# Lumos_Probe.net
KiCad netlist of a schematic drawn in Altium Designer
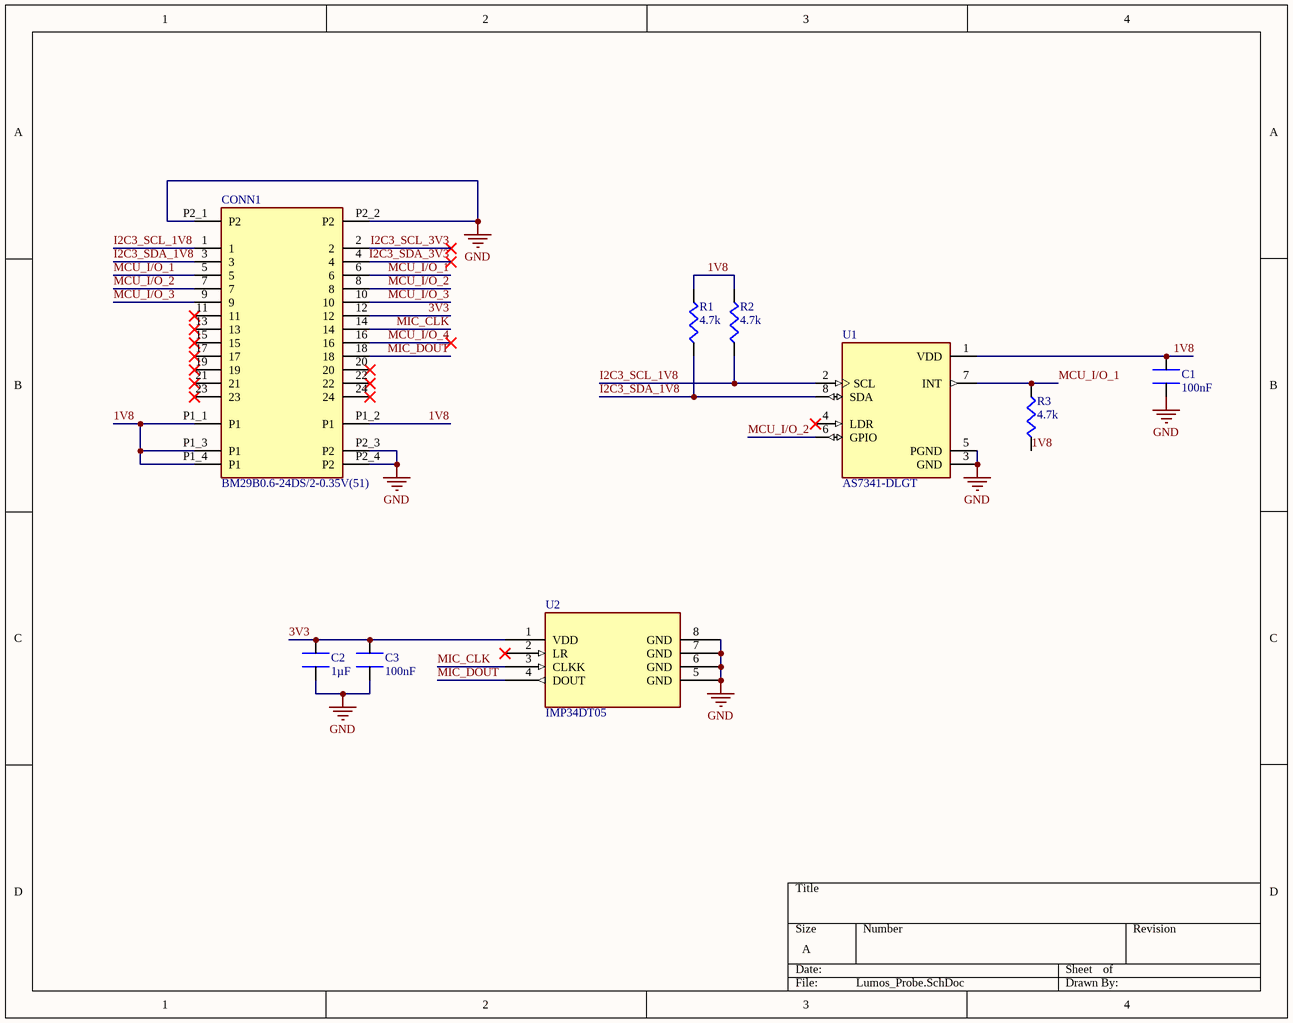
[diagram p0: Lumos_Probe.SchDoc]

(export (version "E")
  (design (tool "Eeschema 10.0.6"))
  (components
    (comp (ref "C1")
      (value "100nF")
      (footprint "Chip2PinSM127P600-8N")
      (fields
        (field (name "MANUFACTURER") "KYOCERA AVX")
        (field (name "MANUFACTURER PART NUMBER") "0402YC104JAT4A")
      )
      (libsource (lib "Lumos_Probe") (part "CMP-00047-1"))
    )
    (comp (ref "C2")
      (value "1µF")
      (footprint "Chip2PinSM127P600-8N")
      (fields
        (field (name "MANUFACTURER") "KYOCERA AVX")
        (field (name "MANUFACTURER PART NUMBER") "0402YD105KAT4A")
      )
      (libsource (lib "Lumos_Probe") (part "CMP-001-00107-6"))
    )
    (comp (ref "C3")
      (value "100nF")
      (footprint "Chip2PinSM127P600-8N")
      (fields
        (field (name "MANUFACTURER") "KYOCERA AVX")
        (field (name "MANUFACTURER PART NUMBER") "0402YC104JAT4A")
      )
      (libsource (lib "Lumos_Probe") (part "CMP-00047-1"))
    )
    (comp (ref "CONN1")
      (value "BM29B0.6-24DS/2-0.35V(51)")
      (footprint "BM29B0.6-24DS_2-0.35V(51)-Footprint-1")
      (description "Connector Receptacle 26 Pos (24+2) SMD")
      (fields (field (name "MANUFACTURER") "HIROSE ELECTRIC"))
      (libsource (lib "Lumos_Probe") (part "CMP-002-00106-1"))
    )
    (comp (ref "R1")
      (value "4.7k")
      (footprint "Chip2PinSM127P600-8N")
      (fields
        (field (name "TOLERANCE") "5%")
        (field (name "POWER") "50mW")
        (field (name "MANUFACTURER") "Bourns")
      )
      (libsource (lib "Lumos_Probe") (part "CMP-00117-1"))
    )
    (comp (ref "R2")
      (value "4.7k")
      (footprint "Chip2PinSM127P600-8N")
      (fields
        (field (name "TOLERANCE") "5%")
        (field (name "POWER") "50mW")
        (field (name "MANUFACTURER") "Bourns")
      )
      (libsource (lib "Lumos_Probe") (part "CMP-00117-1"))
    )
    (comp (ref "R3")
      (value "4.7k")
      (footprint "Chip2PinSM127P600-8N")
      (fields
        (field (name "TOLERANCE") "5%")
        (field (name "POWER") "50mW")
        (field (name "MANUFACTURER") "Bourns")
      )
      (libsource (lib "Lumos_Probe") (part "CMP-00117-1"))
    )
    (comp (ref "U1")
      (value "AS7341-DLGT")
      (footprint "PSON80P310X200X110-8N")
      (description "Optical Sensor Ambient - IÂ²C 8-TFLGA")
      (fields (field (name "MF") "ams"))
      (libsource (lib "Lumos_Probe") (part "AS7341-DLGT"))
    )
    (comp (ref "U2")
      (value "IMP34DT05")
      (footprint "HCLGA_3X4X1_STM")
      (description "MEMS audio sensor omnidirectional digital microphone for industrial applications")
      (fields (field (name "COPYRIGHT") "Copyright (C) 2025 Ultra Librarian. All rights reserved."))
      (libsource (lib "Lumos_Probe") (part "IMP34DT05"))
    )
  )
  (nets
    (net (code "1") (name "/1V8") (class "Default")
      (node (ref "C1") (pin "1") (pinfunction "1_1") (pintype "passive"))
      (node (ref "CONN1") (pin "P1_1") (pinfunction "P1_P1_1") (pintype "power_in"))
      (node (ref "CONN1") (pin "P1_2") (pinfunction "P1_P1_2") (pintype "power_in"))
      (node (ref "CONN1") (pin "P1_3") (pinfunction "P1_P1_3") (pintype "power_in"))
      (node (ref "CONN1") (pin "P1_4") (pinfunction "P1_P1_4") (pintype "power_in"))
      (node (ref "R1") (pin "1") (pinfunction "1_1") (pintype "passive"))
      (node (ref "R2") (pin "1") (pinfunction "1_1") (pintype "passive"))
      (node (ref "R3") (pin "1") (pinfunction "1_1") (pintype "passive"))
      (node (ref "U1") (pin "1") (pinfunction "VDD_1") (pintype "power_in"))
    )
    (net (code "2") (name "/3V3") (class "Default")
      (node (ref "C2") (pin "1") (pinfunction "1_1") (pintype "passive"))
      (node (ref "C3") (pin "1") (pinfunction "1_1") (pintype "passive"))
      (node (ref "CONN1") (pin "12") (pinfunction "12_12") (pintype "passive"))
      (node (ref "U2") (pin "1") (pinfunction "VDD_1") (pintype "power_in"))
    )
    (net (code "3") (name "/I2C3_SCL_1V8") (class "Default")
      (node (ref "CONN1") (pin "1") (pinfunction "1_1") (pintype "passive"))
      (node (ref "R2") (pin "2") (pinfunction "2_2") (pintype "passive"))
      (node (ref "U1") (pin "2") (pinfunction "SCL_2") (pintype "input"))
    )
    (net (code "4") (name "/I2C3_SCL_3V3") (class "Default")
      (node (ref "CONN1") (pin "2") (pinfunction "2_2") (pintype "passive+no_connect"))
    )
    (net (code "5") (name "/I2C3_SDA_1V8") (class "Default")
      (node (ref "CONN1") (pin "3") (pinfunction "3_3") (pintype "passive"))
      (node (ref "R1") (pin "2") (pinfunction "2_2") (pintype "passive"))
      (node (ref "U1") (pin "8") (pinfunction "SDA_8") (pintype "bidirectional"))
    )
    (net (code "6") (name "/I2C3_SDA_3V3") (class "Default")
      (node (ref "CONN1") (pin "4") (pinfunction "4_4") (pintype "passive+no_connect"))
    )
    (net (code "7") (name "/MCU_I{slash}O_1") (class "Default")
      (node (ref "CONN1") (pin "5") (pinfunction "5_5") (pintype "passive"))
      (node (ref "CONN1") (pin "6") (pinfunction "6_6") (pintype "passive"))
      (node (ref "R3") (pin "2") (pinfunction "2_2") (pintype "passive"))
      (node (ref "U1") (pin "7") (pinfunction "INT_7") (pintype "output"))
    )
    (net (code "8") (name "/MCU_I{slash}O_2") (class "Default")
      (node (ref "CONN1") (pin "7") (pinfunction "7_7") (pintype "passive"))
      (node (ref "CONN1") (pin "8") (pinfunction "8_8") (pintype "passive"))
      (node (ref "U1") (pin "6") (pinfunction "GPIO_6") (pintype "bidirectional"))
    )
    (net (code "9") (name "/MCU_I{slash}O_3") (class "Default")
      (node (ref "CONN1") (pin "10") (pinfunction "10_10") (pintype "passive"))
      (node (ref "CONN1") (pin "9") (pinfunction "9_9") (pintype "passive"))
    )
    (net (code "10") (name "/MCU_I{slash}O_4") (class "Default")
      (node (ref "CONN1") (pin "16") (pinfunction "16_16") (pintype "passive+no_connect"))
    )
    (net (code "11") (name "/MIC_CLK") (class "Default")
      (node (ref "CONN1") (pin "14") (pinfunction "14_14") (pintype "passive"))
      (node (ref "U2") (pin "3") (pinfunction "CLKK_3") (pintype "input"))
    )
    (net (code "12") (name "/MIC_DOUT") (class "Default")
      (node (ref "CONN1") (pin "18") (pinfunction "18_18") (pintype "passive"))
      (node (ref "U2") (pin "4") (pinfunction "DOUT_4") (pintype "output"))
    )
    (net (code "13") (name "GND") (class "Default")
      (node (ref "C1") (pin "2") (pinfunction "2_2") (pintype "passive"))
      (node (ref "C2") (pin "2") (pinfunction "2_2") (pintype "passive"))
      (node (ref "C3") (pin "2") (pinfunction "2_2") (pintype "passive"))
      (node (ref "CONN1") (pin "P2_1") (pinfunction "P2_P2_1") (pintype "power_in"))
      (node (ref "CONN1") (pin "P2_2") (pinfunction "P2_P2_2") (pintype "power_in"))
      (node (ref "CONN1") (pin "P2_3") (pinfunction "P2_P2_3") (pintype "power_in"))
      (node (ref "CONN1") (pin "P2_4") (pinfunction "P2_P2_4") (pintype "power_in"))
      (node (ref "U1") (pin "3") (pinfunction "GND_3") (pintype "power_in"))
      (node (ref "U1") (pin "5") (pinfunction "PGND_5") (pintype "power_in"))
      (node (ref "U2") (pin "5") (pinfunction "GND_5") (pintype "power_in"))
      (node (ref "U2") (pin "6") (pinfunction "GND_6") (pintype "power_in"))
      (node (ref "U2") (pin "7") (pinfunction "GND_7") (pintype "power_in"))
      (node (ref "U2") (pin "8") (pinfunction "GND_8") (pintype "power_in"))
    )
    (net (code "14") (name "unconnected-(CONN1-Pad11)") (class "Default")
      (node (ref "CONN1") (pin "11") (pinfunction "11_11") (pintype "passive+no_connect"))
    )
    (net (code "15") (name "unconnected-(CONN1-Pad13)") (class "Default")
      (node (ref "CONN1") (pin "13") (pinfunction "13_13") (pintype "passive+no_connect"))
    )
    (net (code "16") (name "unconnected-(CONN1-Pad15)") (class "Default")
      (node (ref "CONN1") (pin "15") (pinfunction "15_15") (pintype "passive+no_connect"))
    )
    (net (code "17") (name "unconnected-(CONN1-Pad17)") (class "Default")
      (node (ref "CONN1") (pin "17") (pinfunction "17_17") (pintype "passive+no_connect"))
    )
    (net (code "18") (name "unconnected-(CONN1-Pad19)") (class "Default")
      (node (ref "CONN1") (pin "19") (pinfunction "19_19") (pintype "passive+no_connect"))
    )
    (net (code "19") (name "unconnected-(CONN1-Pad20)") (class "Default")
      (node (ref "CONN1") (pin "20") (pinfunction "20_20") (pintype "passive+no_connect"))
    )
    (net (code "20") (name "unconnected-(CONN1-Pad21)") (class "Default")
      (node (ref "CONN1") (pin "21") (pinfunction "21_21") (pintype "passive+no_connect"))
    )
    (net (code "21") (name "unconnected-(CONN1-Pad22)") (class "Default")
      (node (ref "CONN1") (pin "22") (pinfunction "22_22") (pintype "passive+no_connect"))
    )
    (net (code "22") (name "unconnected-(CONN1-Pad23)") (class "Default")
      (node (ref "CONN1") (pin "23") (pinfunction "23_23") (pintype "passive+no_connect"))
    )
    (net (code "23") (name "unconnected-(CONN1-Pad24)") (class "Default")
      (node (ref "CONN1") (pin "24") (pinfunction "24_24") (pintype "passive+no_connect"))
    )
    (net (code "24") (name "unconnected-(U1-LDR-Pad4)") (class "Default")
      (node (ref "U1") (pin "4") (pinfunction "LDR_4") (pintype "input+no_connect"))
    )
    (net (code "25") (name "unconnected-(U2-LR-Pad2)") (class "Default")
      (node (ref "U2") (pin "2") (pinfunction "LR_2") (pintype "input+no_connect"))
    )
  )
)
